# full_schema.net
KiCad netlist of a schematic drawn in EAGLE
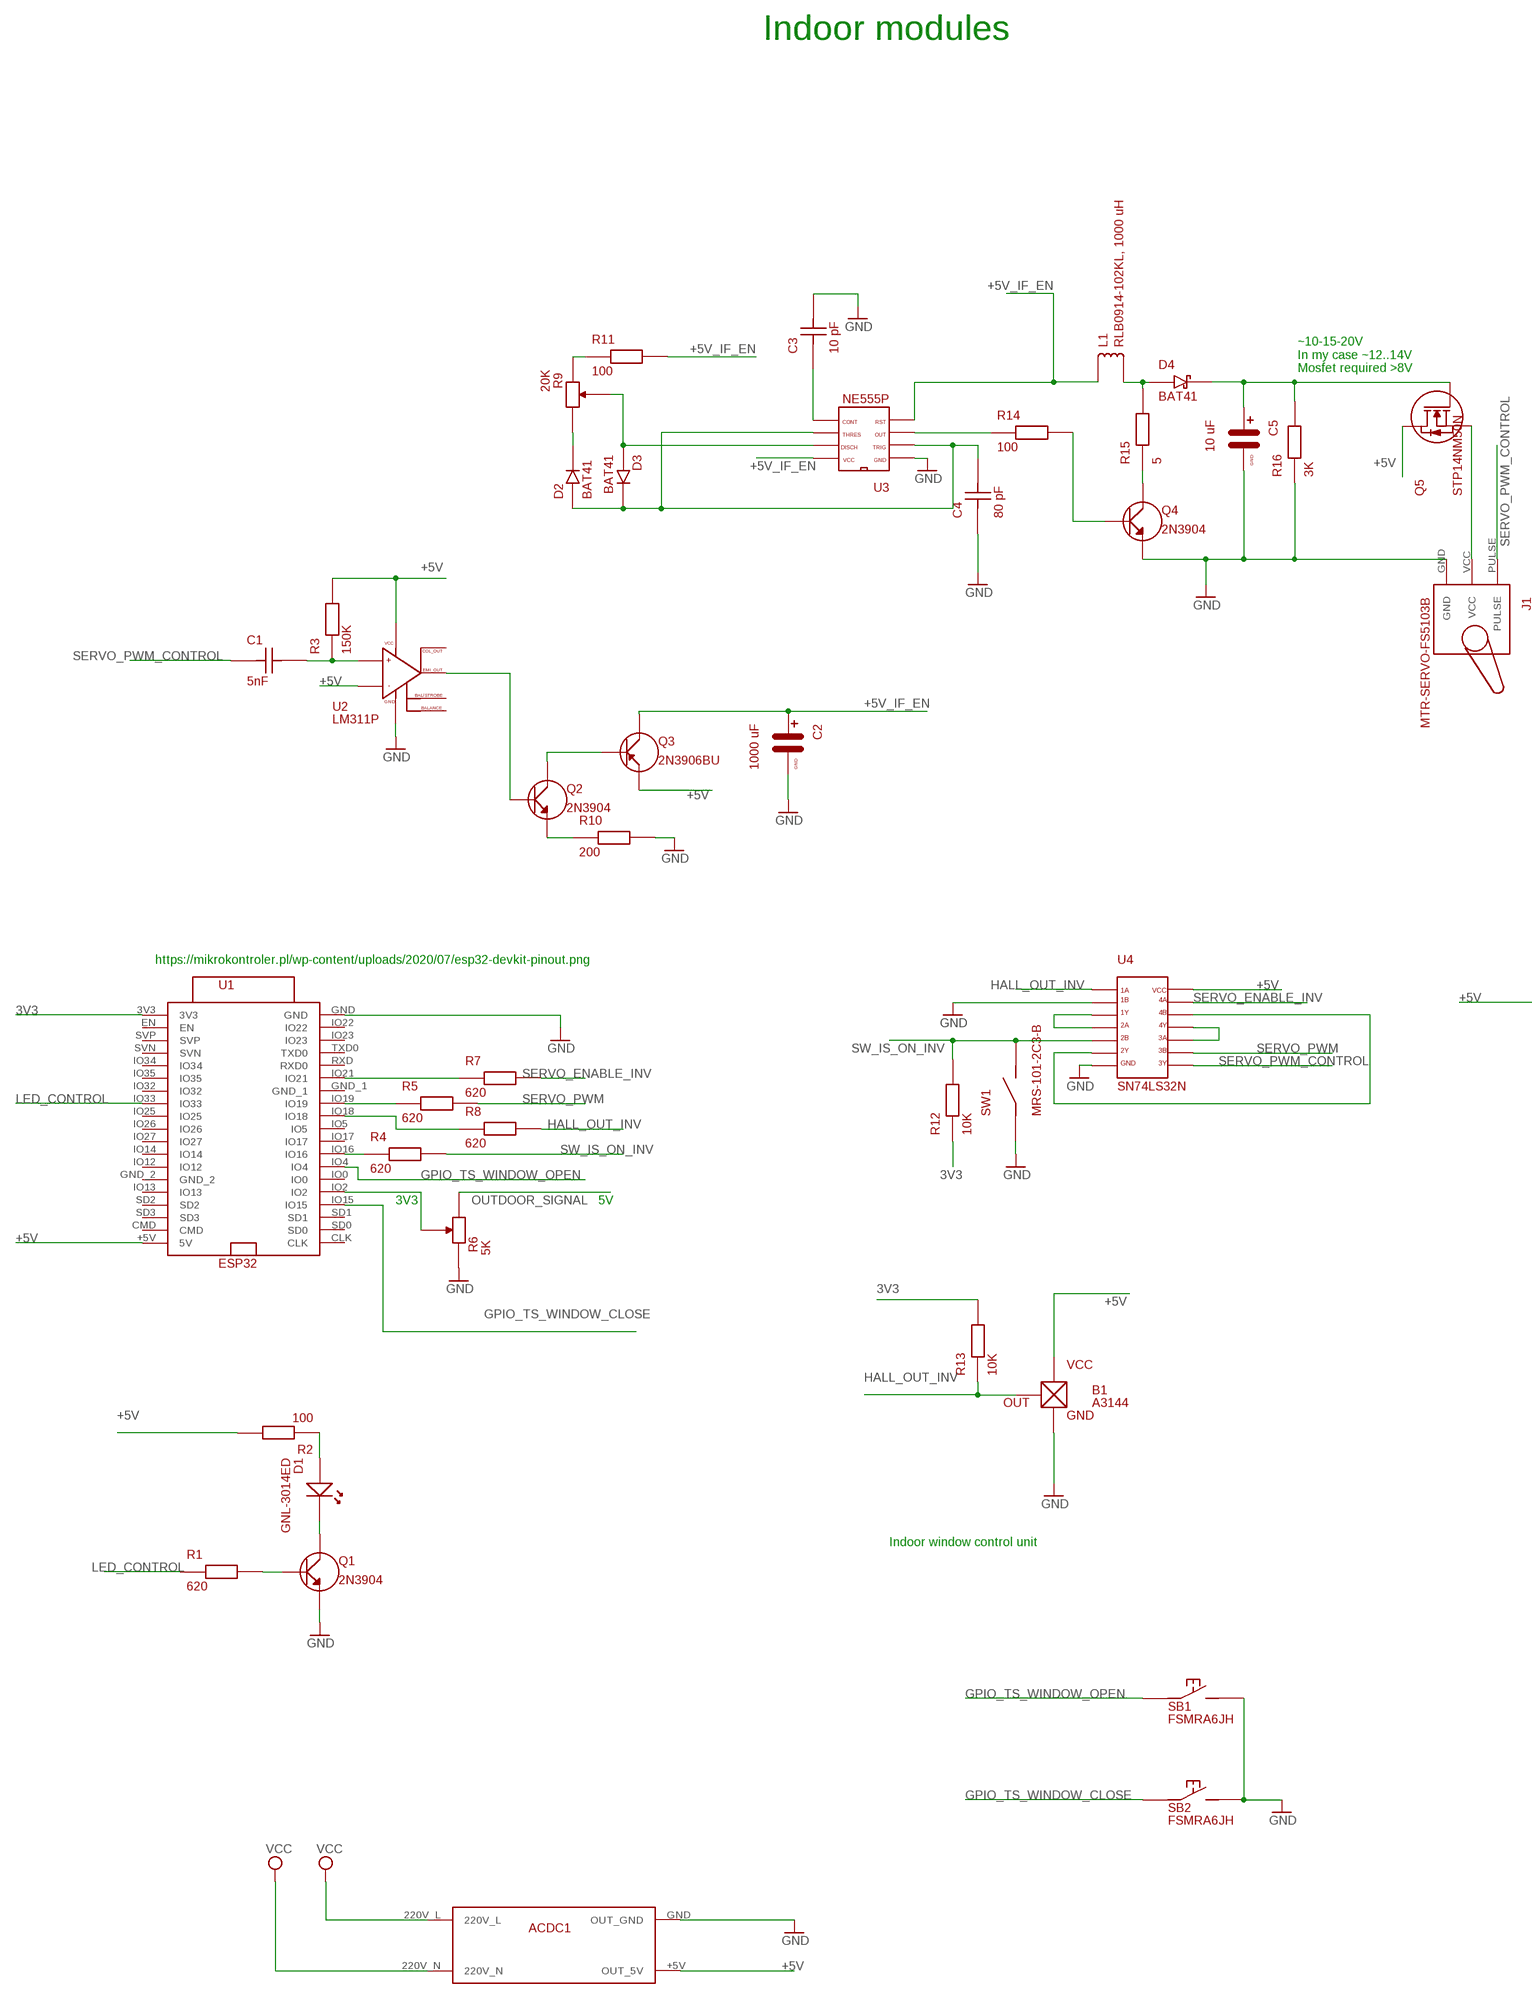
[diagram p0: schematic, sheet 1, part 1 of 2]
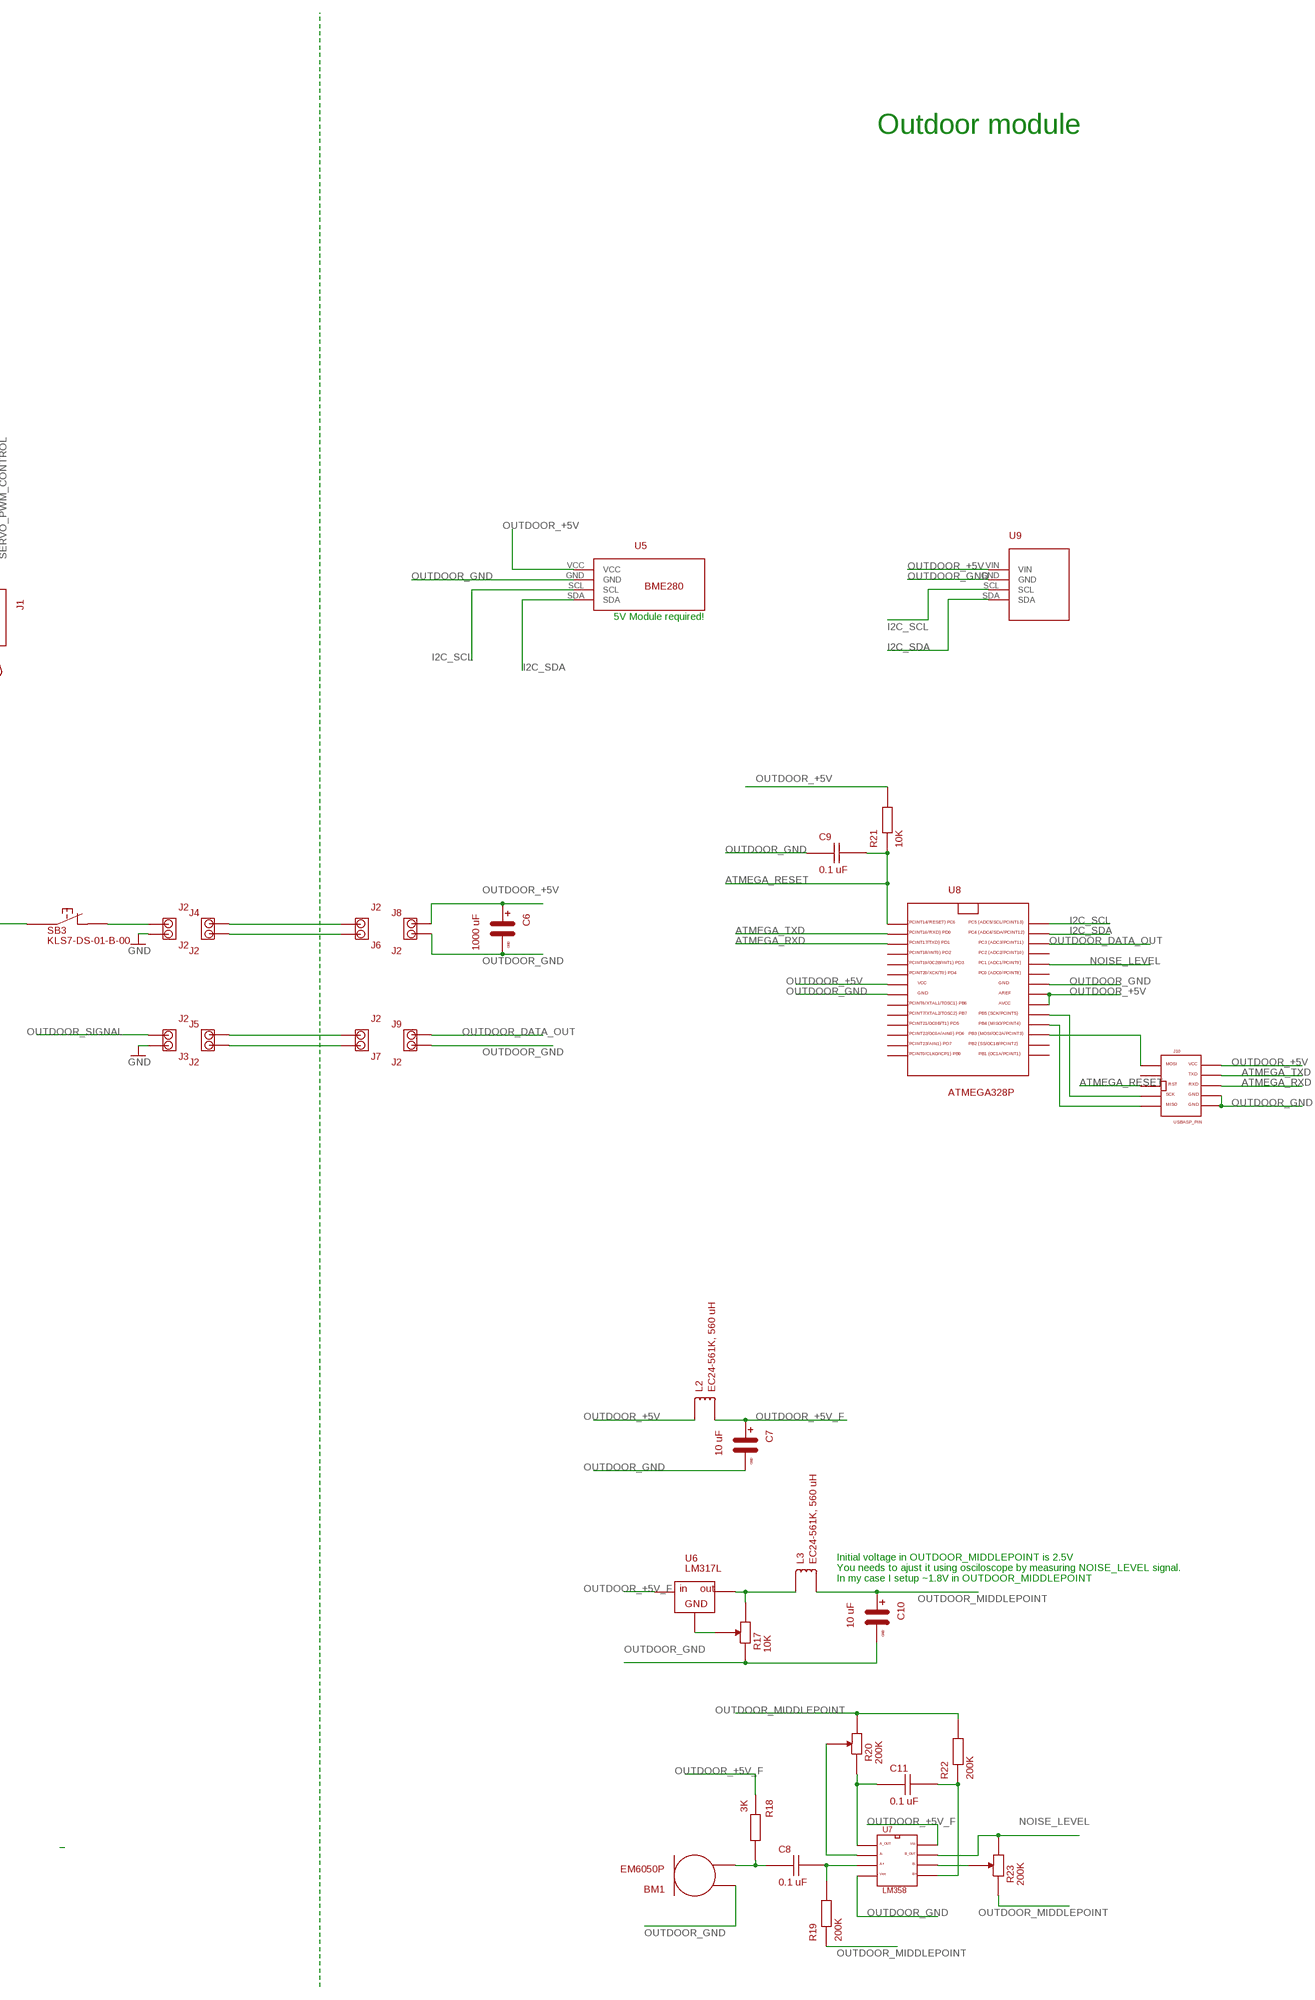
[diagram p1: schematic, sheet 1, part 2 of 2]

(export (version "E")
  (design (tool "Eeschema 10.0.6"))
  (components
    (comp (ref "ACDC1")
      (value "ACDC")
      (footprint "eagle-import:ACDC")
      (libsource (lib "eagle-import") (part "ACDC"))
    )
    (comp (ref "B1")
      (value "A3144")
      (footprint "eagle-import:HALL_SENSOR")
      (libsource (lib "eagle-import") (part "HALL_SENSOR"))
    )
    (comp (ref "BM1")
      (value "EM6050P")
      (footprint "eagle-import:MICROPHONE")
      (libsource (lib "eagle-import") (part "MICROPHONE"))
    )
    (comp (ref "C1")
      (value "5nF")
      (footprint "eagle-import:C-1")
      (libsource (lib "eagle-import") (part "C-1"))
    )
    (comp (ref "C2")
      (value "1000 uF")
      (footprint "eagle-import:C")
      (libsource (lib "eagle-import") (part "C"))
    )
    (comp (ref "C3")
      (value "10 pF")
      (footprint "eagle-import:C-1")
      (libsource (lib "eagle-import") (part "C-1"))
    )
    (comp (ref "C4")
      (value "80 pF")
      (footprint "eagle-import:C-1")
      (libsource (lib "eagle-import") (part "C-1"))
    )
    (comp (ref "C5") (value "10 uF") (footprint "eagle-import:C") (libsource (lib "eagle-import") (part "C")))
    (comp (ref "C6")
      (value "1000 uF")
      (footprint "eagle-import:C")
      (libsource (lib "eagle-import") (part "C"))
    )
    (comp (ref "C7") (value "10 uF") (footprint "eagle-import:C") (libsource (lib "eagle-import") (part "C")))
    (comp (ref "C8")
      (value "0.1 uF")
      (footprint "eagle-import:C-1")
      (libsource (lib "eagle-import") (part "C-1"))
    )
    (comp (ref "C9")
      (value "0.1 uF")
      (footprint "eagle-import:C-1")
      (libsource (lib "eagle-import") (part "C-1"))
    )
    (comp (ref "C10")
      (value "10 uF")
      (footprint "eagle-import:C")
      (libsource (lib "eagle-import") (part "C"))
    )
    (comp (ref "C11")
      (value "0.1 uF")
      (footprint "eagle-import:C-1")
      (libsource (lib "eagle-import") (part "C-1"))
    )
    (comp (ref "D1")
      (value "GNL-3014ED")
      (footprint "eagle-import:LD")
      (libsource (lib "eagle-import") (part "LD"))
    )
    (comp (ref "D2") (value "BAT41") (footprint "eagle-import:D") (libsource (lib "eagle-import") (part "D")))
    (comp (ref "D3") (value "BAT41") (footprint "eagle-import:D") (libsource (lib "eagle-import") (part "D")))
    (comp (ref "D4")
      (value "BAT41")
      (footprint "eagle-import:D_SCHOTTKY")
      (libsource (lib "eagle-import") (part "D_SCHOTTKY"))
    )
    (comp (ref "J1")
      (value "MTR-SERVO-FS5103B")
      (footprint "eagle-import:SERVO")
      (libsource (lib "eagle-import") (part "SERVO"))
    )
    (comp (ref "J2") (value "J2") (footprint "eagle-import:J2") (libsource (lib "eagle-import") (part "J2")))
    (comp (ref "J3") (value "J2") (footprint "eagle-import:J2") (libsource (lib "eagle-import") (part "J2")))
    (comp (ref "J4") (value "J2") (footprint "eagle-import:J2") (libsource (lib "eagle-import") (part "J2")))
    (comp (ref "J5") (value "J2") (footprint "eagle-import:J2") (libsource (lib "eagle-import") (part "J2")))
    (comp (ref "J6") (value "J2") (footprint "eagle-import:J2") (libsource (lib "eagle-import") (part "J2")))
    (comp (ref "J7") (value "J2") (footprint "eagle-import:J2") (libsource (lib "eagle-import") (part "J2")))
    (comp (ref "J8") (value "J2") (footprint "eagle-import:J2") (libsource (lib "eagle-import") (part "J2")))
    (comp (ref "J9") (value "J2") (footprint "eagle-import:J2") (libsource (lib "eagle-import") (part "J2")))
    (comp (ref "J10")
      (value "USBASP_PIN")
      (footprint "eagle-import:USBASP_PIN")
      (libsource (lib "eagle-import") (part "USBASP_PIN"))
    )
    (comp (ref "L1")
      (value "RLB0914-102KL, 1000 uH")
      (footprint "eagle-import:L-RLB0914")
      (libsource (lib "eagle-import") (part "L"))
    )
    (comp (ref "L2")
      (value "EC24-561K, 560 uH")
      (footprint "eagle-import:L-EC24")
      (libsource (lib "eagle-import") (part "LL-EC24"))
    )
    (comp (ref "L3")
      (value "EC24-561K, 560 uH")
      (footprint "eagle-import:L-EC24")
      (libsource (lib "eagle-import") (part "LL-EC24"))
    )
    (comp (ref "Q1")
      (value "2N3904")
      (footprint "eagle-import:TRANSISTOR")
      (libsource (lib "eagle-import") (part "TRANSISTOR_NPN"))
    )
    (comp (ref "Q2")
      (value "2N3904")
      (footprint "eagle-import:TRANSISTOR")
      (libsource (lib "eagle-import") (part "TRANSISTOR_NPN"))
    )
    (comp (ref "Q3")
      (value "2N3906BU")
      (footprint "eagle-import:TRANSISTOR")
      (libsource (lib "eagle-import") (part "TRANSISTOR_PNP"))
    )
    (comp (ref "Q4")
      (value "2N3904")
      (footprint "eagle-import:TRANSISTOR")
      (libsource (lib "eagle-import") (part "TRANSISTOR_NPN"))
    )
    (comp (ref "Q5")
      (value "STP14NM50N")
      (footprint "eagle-import:MOSFET_N")
      (libsource (lib "eagle-import") (part "MOSFET_N"))
    )
    (comp (ref "R1") (value "620") (footprint "eagle-import:R") (libsource (lib "eagle-import") (part "R")))
    (comp (ref "R2") (value "100") (footprint "eagle-import:R") (libsource (lib "eagle-import") (part "R")))
    (comp (ref "R3") (value "150K") (footprint "eagle-import:R") (libsource (lib "eagle-import") (part "R")))
    (comp (ref "R4") (value "620") (footprint "eagle-import:R") (libsource (lib "eagle-import") (part "R")))
    (comp (ref "R5") (value "620") (footprint "eagle-import:R") (libsource (lib "eagle-import") (part "R")))
    (comp (ref "R6")
      (value "5K")
      (footprint "eagle-import:RD-3362H")
      (libsource (lib "eagle-import") (part "RD"))
    )
    (comp (ref "R7") (value "620") (footprint "eagle-import:R") (libsource (lib "eagle-import") (part "R")))
    (comp (ref "R8") (value "620") (footprint "eagle-import:R") (libsource (lib "eagle-import") (part "R")))
    (comp (ref "R9")
      (value "20K")
      (footprint "eagle-import:RD-3362H")
      (libsource (lib "eagle-import") (part "RD"))
    )
    (comp (ref "R10") (value "200") (footprint "eagle-import:R") (libsource (lib "eagle-import") (part "R")))
    (comp (ref "R11") (value "100") (footprint "eagle-import:R") (libsource (lib "eagle-import") (part "R")))
    (comp (ref "R12") (value "10K") (footprint "eagle-import:R") (libsource (lib "eagle-import") (part "R")))
    (comp (ref "R13") (value "10K") (footprint "eagle-import:R") (libsource (lib "eagle-import") (part "R")))
    (comp (ref "R14") (value "100") (footprint "eagle-import:R") (libsource (lib "eagle-import") (part "R")))
    (comp (ref "R15") (value "5") (footprint "eagle-import:R") (libsource (lib "eagle-import") (part "R")))
    (comp (ref "R16") (value "3K") (footprint "eagle-import:R") (libsource (lib "eagle-import") (part "R")))
    (comp (ref "R17")
      (value "10K")
      (footprint "eagle-import:RD-3362H")
      (libsource (lib "eagle-import") (part "RD"))
    )
    (comp (ref "R18") (value "3K") (footprint "eagle-import:R") (libsource (lib "eagle-import") (part "R")))
    (comp (ref "R19") (value "200K") (footprint "eagle-import:R") (libsource (lib "eagle-import") (part "R")))
    (comp (ref "R20")
      (value "200K")
      (footprint "eagle-import:RD-3296Z")
      (libsource (lib "eagle-import") (part "RD3296-Z"))
    )
    (comp (ref "R21") (value "10K") (footprint "eagle-import:R") (libsource (lib "eagle-import") (part "R")))
    (comp (ref "R22") (value "200K") (footprint "eagle-import:R") (libsource (lib "eagle-import") (part "R")))
    (comp (ref "R23")
      (value "200K")
      (footprint "eagle-import:RD-3296Z")
      (libsource (lib "eagle-import") (part "RD3296-Z"))
    )
    (comp (ref "SB1")
      (value "FSMRA6JH")
      (footprint "eagle-import:SB-NO-SPST-ANGLE")
      (libsource (lib "eagle-import") (part "SB-NO"))
    )
    (comp (ref "SB2")
      (value "FSMRA6JH")
      (footprint "eagle-import:SB-NO-SPST-ANGLE")
      (libsource (lib "eagle-import") (part "SB-NO"))
    )
    (comp (ref "SB3")
      (value "KLS7-DS-01-B-00")
      (footprint "eagle-import:SB-NC")
      (libsource (lib "eagle-import") (part "SB-NC"))
    )
    (comp (ref "SW1")
      (value "MRS-101-2C3-B")
      (footprint "eagle-import:SWITCH")
      (libsource (lib "eagle-import") (part "SWITCH"))
    )
    (comp (ref "U1")
      (value "ESP32")
      (footprint "eagle-import:ESP32")
      (libsource (lib "eagle-import") (part "ESP32"))
    )
    (comp (ref "U2")
      (value "LM311P")
      (footprint "eagle-import:DIP8")
      (libsource (lib "eagle-import") (part "LM311P"))
    )
    (comp (ref "U3")
      (value "NE555P")
      (footprint "eagle-import:DIP8")
      (libsource (lib "eagle-import") (part "NE555P"))
    )
    (comp (ref "U4")
      (value "SN74LS32N")
      (footprint "eagle-import:DIP14")
      (libsource (lib "eagle-import") (part "SN74LS32N"))
    )
    (comp (ref "U5")
      (value "BMP280 5V module")
      (footprint "eagle-import:BME280")
      (libsource (lib "eagle-import") (part "BME280"))
    )
    (comp (ref "U6")
      (value "LM317L")
      (footprint "eagle-import:VOLTAGE_REGULATOR")
      (libsource (lib "eagle-import") (part "VOLTAGE_REGULATOR"))
    )
    (comp (ref "U7")
      (value "LM358")
      (footprint "eagle-import:DIP8")
      (libsource (lib "eagle-import") (part "LM358"))
    )
    (comp (ref "U8")
      (value "ATMEGA328P")
      (footprint "eagle-import:ATMEGA328P")
      (libsource (lib "eagle-import") (part "ATMEGA328P"))
    )
    (comp (ref "U9")
      (value "GY-SGP30")
      (footprint "eagle-import:GY-SGP30")
      (libsource (lib "eagle-import") (part "GY-SGP30"))
    )
  )
  (nets
    (net (code "1") (name "/+5V") (class "Default")
      (node (ref "ACDC1") (pin "+5V") (pinfunction "OUT_5V_+5V") (pintype "power_in"))
      (node (ref "B1") (pin "VCC") (pinfunction "VCC_VCC") (pintype "power_in"))
      (node (ref "Q3") (pin "E") (pinfunction "E_E") (pintype "bidirectional"))
      (node (ref "Q5") (pin "D") (pinfunction "D_D") (pintype "bidirectional"))
      (node (ref "R2") (pin "P$2") (pinfunction "P$2_P$2") (pintype "bidirectional"))
      (node (ref "R3") (pin "P$2") (pinfunction "P$2_P$2") (pintype "bidirectional"))
      (node (ref "SB3") (pin "P$1") (pinfunction "P$1_P$1") (pintype "bidirectional"))
      (node (ref "U1") (pin "+5V") (pinfunction "5V_+5V") (pintype "power_in"))
      (node (ref "U2") (pin "PIN_3") (pinfunction "IN-_PIN_3") (pintype "input"))
      (node (ref "U2") (pin "PIN_8") (pinfunction "VCC_PIN_8") (pintype "power_in"))
      (node (ref "U4") (pin "PIN_14") (pinfunction "VCC_PIN_14") (pintype "power_in"))
    )
    (net (code "2") (name "/+5V_IF_EN") (class "Default")
      (node (ref "C2") (pin "PIN_PLUS") (pinfunction "PIN_PLUS_PIN_PLUS") (pintype "bidirectional"))
      (node (ref "L1") (pin "P$1") (pinfunction "P$1_P$1") (pintype "bidirectional"))
      (node (ref "Q3") (pin "C") (pinfunction "C_C") (pintype "bidirectional"))
      (node (ref "R11") (pin "P$2") (pinfunction "P$2_P$2") (pintype "bidirectional"))
      (node (ref "U3") (pin "PIN_4") (pinfunction "RESET_PIN_4") (pintype "bidirectional"))
      (node (ref "U3") (pin "PIN_8") (pinfunction "VCC_PIN_8") (pintype "power_in"))
    )
    (net (code "3") (name "/3V3") (class "Default")
      (node (ref "R12") (pin "P$1") (pinfunction "P$1_P$1") (pintype "bidirectional"))
      (node (ref "R13") (pin "P$2") (pinfunction "P$2_P$2") (pintype "bidirectional"))
      (node (ref "U1") (pin "3V3") (pinfunction "3V3_3V3") (pintype "power_in"))
    )
    (net (code "4") (name "/ATMEGA_RESET") (class "Default")
      (node (ref "C9") (pin "P$2") (pinfunction "P$2_P$2") (pintype "bidirectional"))
      (node (ref "J10") (pin "RST") (pinfunction "RESET_RST") (pintype "bidirectional"))
      (node (ref "R21") (pin "P$1") (pinfunction "P$1_P$1") (pintype "bidirectional"))
      (node (ref "U8") (pin "PC6") (pinfunction "PC6_PC6") (pintype "bidirectional"))
    )
    (net (code "5") (name "/ATMEGA_RXD") (class "Default")
      (node (ref "J10") (pin "RXD") (pinfunction "RXD_RXD") (pintype "bidirectional"))
      (node (ref "U8") (pin "PD1") (pinfunction "PD1_PD1") (pintype "bidirectional"))
    )
    (net (code "6") (name "/ATMEGA_TXD") (class "Default")
      (node (ref "J10") (pin "TXD") (pinfunction "TXD_TXD") (pintype "bidirectional"))
      (node (ref "U8") (pin "PD0") (pinfunction "PD0_PD0") (pintype "bidirectional"))
    )
    (net (code "7") (name "/GPIO_TS_WINDOW_CLOSE") (class "Default")
      (node (ref "SB2") (pin "A") (pinfunction "P$1_A") (pintype "bidirectional"))
      (node (ref "U1") (pin "IO15") (pinfunction "IO15_IO15") (pintype "bidirectional"))
    )
    (net (code "8") (name "/GPIO_TS_WINDOW_OPEN") (class "Default")
      (node (ref "SB1") (pin "A") (pinfunction "P$1_A") (pintype "bidirectional"))
      (node (ref "U1") (pin "IO4") (pinfunction "IO4_IO4") (pintype "bidirectional"))
    )
    (net (code "9") (name "/HALL_OUT_INV") (class "Default")
      (node (ref "B1") (pin "OUT") (pinfunction "OUT_OUT") (pintype "bidirectional"))
      (node (ref "R13") (pin "P$1") (pinfunction "P$1_P$1") (pintype "bidirectional"))
      (node (ref "R8") (pin "P$2") (pinfunction "P$2_P$2") (pintype "bidirectional"))
      (node (ref "U4") (pin "PIN_1") (pinfunction "1A_PIN_1") (pintype "input"))
    )
    (net (code "10") (name "/I2C_SCL") (class "Default")
      (node (ref "U5") (pin "SCL") (pinfunction "SCL_SCL") (pintype "bidirectional"))
      (node (ref "U8") (pin "PC5") (pinfunction "PC5_PC5") (pintype "bidirectional"))
      (node (ref "U9") (pin "SCL") (pinfunction "SCL_SCL") (pintype "bidirectional"))
    )
    (net (code "11") (name "/I2C_SDA") (class "Default")
      (node (ref "U5") (pin "SDA") (pinfunction "SDA_SDA") (pintype "bidirectional"))
      (node (ref "U8") (pin "PC4") (pinfunction "PC4_PC4") (pintype "bidirectional"))
      (node (ref "U9") (pin "SDA") (pinfunction "SDA_SDA") (pintype "bidirectional"))
    )
    (net (code "12") (name "/LED_CONTROL") (class "Default")
      (node (ref "R1") (pin "P$1") (pinfunction "P$1_P$1") (pintype "bidirectional"))
      (node (ref "U1") (pin "IO33") (pinfunction "IO33_IO33") (pintype "bidirectional"))
    )
    (net (code "13") (name "/NOISE_LEVEL") (class "Default")
      (node (ref "R23") (pin "P2") (pinfunction "P2_P2") (pintype "bidirectional"))
      (node (ref "U7") (pin "PIN_7") (pinfunction "B_OUT_PIN_7") (pintype "output"))
      (node (ref "U8") (pin "PC1") (pinfunction "PC1_PC1") (pintype "bidirectional"))
    )
    (net (code "14") (name "/OUTDOOR_+5V") (class "Default")
      (node (ref "C6") (pin "PIN_PLUS") (pinfunction "PIN_PLUS_PIN_PLUS") (pintype "bidirectional"))
      (node (ref "J10") (pin "VCC") (pinfunction "VCC_VCC") (pintype "power_in"))
      (node (ref "J8") (pin "PIN_1") (pinfunction "PIN_1_PIN_1") (pintype "bidirectional"))
      (node (ref "L2") (pin "P$1") (pinfunction "P$1_P$1") (pintype "bidirectional"))
      (node (ref "R21") (pin "P$2") (pinfunction "P$2_P$2") (pintype "bidirectional"))
      (node (ref "U5") (pin "VCC") (pinfunction "VCC_VCC") (pintype "power_in"))
      (node (ref "U8") (pin "AREF") (pinfunction "AREF_AREF") (pintype "bidirectional"))
      (node (ref "U8") (pin "AVCC") (pinfunction "AVCC_AVCC") (pintype "power_in"))
      (node (ref "U8") (pin "VCC") (pinfunction "VCC_VCC") (pintype "power_in"))
      (node (ref "U9") (pin "VIN") (pinfunction "VIN_VIN") (pintype "power_in"))
    )
    (net (code "15") (name "/OUTDOOR_+5V_F") (class "Default")
      (node (ref "C7") (pin "PIN_PLUS") (pinfunction "PIN_PLUS_PIN_PLUS") (pintype "bidirectional"))
      (node (ref "L2") (pin "P$2") (pinfunction "P$2_P$2") (pintype "bidirectional"))
      (node (ref "R18") (pin "P$1") (pinfunction "P$1_P$1") (pintype "bidirectional"))
      (node (ref "U6") (pin "IN") (pinfunction "IN_IN") (pintype "power_in"))
      (node (ref "U7") (pin "PIN_8") (pinfunction "VCC_PIN_8") (pintype "power_in"))
    )
    (net (code "16") (name "/OUTDOOR_DATA_OUT") (class "Default")
      (node (ref "J9") (pin "PIN_1") (pinfunction "PIN_1_PIN_1") (pintype "bidirectional"))
      (node (ref "U8") (pin "PC3") (pinfunction "PC3_PC3") (pintype "bidirectional"))
    )
    (net (code "17") (name "/OUTDOOR_GND") (class "Default")
      (node (ref "BM1") (pin "P$1") (pinfunction "P$1_P$1") (pintype "bidirectional"))
      (node (ref "C10") (pin "PIN_GND") (pinfunction "PIN_GND_PIN_GND") (pintype "bidirectional"))
      (node (ref "C6") (pin "PIN_GND") (pinfunction "PIN_GND_PIN_GND") (pintype "bidirectional"))
      (node (ref "C7") (pin "PIN_GND") (pinfunction "PIN_GND_PIN_GND") (pintype "bidirectional"))
      (node (ref "C9") (pin "P$1") (pinfunction "P$1_P$1") (pintype "bidirectional"))
      (node (ref "J10") (pin "GND") (pinfunction "GND_GND") (pintype "power_in"))
      (node (ref "J10") (pin "GND1") (pinfunction "GND1_GND1") (pintype "power_in"))
      (node (ref "J8") (pin "PIN_2") (pinfunction "PIN_2_PIN_2") (pintype "bidirectional"))
      (node (ref "J9") (pin "PIN_2") (pinfunction "PIN_2_PIN_2") (pintype "bidirectional"))
      (node (ref "R17") (pin "P1") (pinfunction "P1_P1") (pintype "bidirectional"))
      (node (ref "U5") (pin "GND") (pinfunction "GND_GND") (pintype "power_in"))
      (node (ref "U7") (pin "PIN_4") (pinfunction "VEE_PIN_4") (pintype "power_in"))
      (node (ref "U8") (pin "GND") (pinfunction "GND_GND") (pintype "power_in"))
      (node (ref "U8") (pin "GND1") (pinfunction "GND1_GND1") (pintype "power_in"))
      (node (ref "U9") (pin "GND") (pinfunction "GND_GND") (pintype "power_in"))
    )
    (net (code "18") (name "/OUTDOOR_MIDDLEPOINT") (class "Default")
      (node (ref "C10") (pin "PIN_PLUS") (pinfunction "PIN_PLUS_PIN_PLUS") (pintype "bidirectional"))
      (node (ref "L3") (pin "P$2") (pinfunction "P$2_P$2") (pintype "bidirectional"))
      (node (ref "R19") (pin "P$1") (pinfunction "P$1_P$1") (pintype "bidirectional"))
      (node (ref "R20") (pin "P2") (pinfunction "P2_P2") (pintype "bidirectional"))
      (node (ref "R22") (pin "P$2") (pinfunction "P$2_P$2") (pintype "bidirectional"))
      (node (ref "R23") (pin "P1") (pinfunction "P1_P1") (pintype "bidirectional"))
    )
    (net (code "19") (name "/OUTDOOR_SIGNAL") (class "Default")
      (node (ref "J3") (pin "PIN_2") (pinfunction "PIN_2_PIN_2") (pintype "bidirectional"))
      (node (ref "R6") (pin "P2") (pinfunction "P2_P2") (pintype "bidirectional"))
    )
    (net (code "20") (name "/SERVO_ENABLE_INV") (class "Default")
      (node (ref "R7") (pin "P$2") (pinfunction "P$2_P$2") (pintype "bidirectional"))
      (node (ref "U4") (pin "PIN_13") (pinfunction "4A_PIN_13") (pintype "input"))
    )
    (net (code "21") (name "/SERVO_PWM") (class "Default")
      (node (ref "R5") (pin "P$2") (pinfunction "P$2_P$2") (pintype "bidirectional"))
      (node (ref "U4") (pin "PIN_9") (pinfunction "3B_PIN_9") (pintype "input"))
    )
    (net (code "22") (name "/SERVO_PWM_CONTROL") (class "Default")
      (node (ref "C1") (pin "P$1") (pinfunction "P$1_P$1") (pintype "bidirectional"))
      (node (ref "J1") (pin "PULSE") (pinfunction "PULSE_PULSE") (pintype "input"))
      (node (ref "U4") (pin "PIN_8") (pinfunction "3Y_PIN_8") (pintype "output"))
    )
    (net (code "23") (name "/SW_IS_ON_INV") (class "Default")
      (node (ref "R12") (pin "P$2") (pinfunction "P$2_P$2") (pintype "bidirectional"))
      (node (ref "R4") (pin "P$2") (pinfunction "P$2_P$2") (pintype "bidirectional"))
      (node (ref "SW1") (pin "P$2") (pinfunction "P$2_P$2") (pintype "bidirectional"))
      (node (ref "U4") (pin "PIN_5") (pinfunction "2B_PIN_5") (pintype "input"))
    )
    (net (code "24") (name "GND") (class "Default")
      (node (ref "ACDC1") (pin "GND") (pinfunction "OUT_GND_GND") (pintype "power_in"))
      (node (ref "B1") (pin "GND") (pinfunction "GND_GND") (pintype "power_in"))
      (node (ref "C2") (pin "PIN_GND") (pinfunction "PIN_GND_PIN_GND") (pintype "bidirectional"))
      (node (ref "C3") (pin "P$2") (pinfunction "P$2_P$2") (pintype "bidirectional"))
      (node (ref "C4") (pin "P$1") (pinfunction "P$1_P$1") (pintype "bidirectional"))
      (node (ref "C5") (pin "PIN_GND") (pinfunction "PIN_GND_PIN_GND") (pintype "bidirectional"))
      (node (ref "J1") (pin "GND") (pinfunction "GND_GND") (pintype "power_in"))
      (node (ref "J2") (pin "PIN_1") (pinfunction "PIN_1_PIN_1") (pintype "bidirectional"))
      (node (ref "J3") (pin "PIN_1") (pinfunction "PIN_1_PIN_1") (pintype "bidirectional"))
      (node (ref "Q1") (pin "E") (pinfunction "E_E") (pintype "bidirectional"))
      (node (ref "Q4") (pin "E") (pinfunction "E_E") (pintype "bidirectional"))
      (node (ref "R10") (pin "P$2") (pinfunction "P$2_P$2") (pintype "bidirectional"))
      (node (ref "R16") (pin "P$1") (pinfunction "P$1_P$1") (pintype "bidirectional"))
      (node (ref "R6") (pin "P1") (pinfunction "P1_P1") (pintype "bidirectional"))
      (node (ref "SB1") (pin "B") (pinfunction "P$2_B") (pintype "bidirectional"))
      (node (ref "SB2") (pin "B") (pinfunction "P$2_B") (pintype "bidirectional"))
      (node (ref "SW1") (pin "P$1") (pinfunction "P$1_P$1") (pintype "bidirectional"))
      (node (ref "U1") (pin "GND") (pinfunction "GND_GND") (pintype "power_in"))
      (node (ref "U2") (pin "PIN_4") (pinfunction "GND_PIN_4") (pintype "power_in"))
      (node (ref "U3") (pin "PIN_1") (pinfunction "GND_PIN_1") (pintype "power_in"))
      (node (ref "U4") (pin "PIN_2") (pinfunction "1B_PIN_2") (pintype "input"))
      (node (ref "U4") (pin "PIN_7") (pinfunction "GND_PIN_7") (pintype "power_in"))
    )
    (net (code "25") (name "Net-(BM1-PadP$2)") (class "Default")
      (node (ref "BM1") (pin "P$2") (pinfunction "P$2_P$2") (pintype "bidirectional"))
      (node (ref "C8") (pin "P$1") (pinfunction "P$1_P$1") (pintype "bidirectional"))
      (node (ref "R18") (pin "P$2") (pinfunction "P$2_P$2") (pintype "bidirectional"))
    )
    (net (code "26") (name "Net-(C5-PadPIN_PLUS)") (class "Default")
      (node (ref "C5") (pin "PIN_PLUS") (pinfunction "PIN_PLUS_PIN_PLUS") (pintype "bidirectional"))
      (node (ref "D4") (pin "CATHODE") (pinfunction "CATHODE_CATHODE") (pintype "bidirectional"))
      (node (ref "Q5") (pin "G") (pinfunction "G_G") (pintype "bidirectional"))
      (node (ref "R16") (pin "P$2") (pinfunction "P$2_P$2") (pintype "bidirectional"))
    )
    (net (code "27") (name "Net-(D1-PadPIN_ANODE)") (class "Default")
      (node (ref "D1") (pin "PIN_ANODE") (pinfunction "PIN_ANODE_PIN_ANODE") (pintype "bidirectional"))
      (node (ref "Q1") (pin "C") (pinfunction "C_C") (pintype "bidirectional"))
    )
    (net (code "28") (name "Net-(D1-PadPIN_CATHODE)") (class "Default")
      (node (ref "D1") (pin "PIN_CATHODE") (pinfunction "PIN_CATHODE_PIN_CATHODE") (pintype "bidirectional"))
      (node (ref "R2") (pin "P$1") (pinfunction "P$1_P$1") (pintype "bidirectional"))
    )
    (net (code "29") (name "Net-(D2-PadP$2)") (class "Default")
      (node (ref "D2") (pin "P$2") (pinfunction "P$2_P$2") (pintype "bidirectional"))
      (node (ref "R9") (pin "P2") (pinfunction "P2_P2") (pintype "bidirectional"))
    )
    (net (code "30") (name "Net-(D4-PadANODE)") (class "Default")
      (node (ref "D4") (pin "ANODE") (pinfunction "ANODE_ANODE") (pintype "bidirectional"))
      (node (ref "L1") (pin "P$2") (pinfunction "P$2_P$2") (pintype "bidirectional"))
      (node (ref "R15") (pin "P$2") (pinfunction "P$2_P$2") (pintype "bidirectional"))
    )
    (net (code "31") (name "Net-(J1-PadVCC)") (class "Default")
      (node (ref "J1") (pin "VCC") (pinfunction "VCC_VCC") (pintype "power_in"))
      (node (ref "Q5") (pin "S") (pinfunction "S_S") (pintype "bidirectional"))
    )
    (net (code "32") (name "Net-(J2-PadPIN_2)") (class "Default")
      (node (ref "J2") (pin "PIN_2") (pinfunction "PIN_2_PIN_2") (pintype "bidirectional"))
      (node (ref "SB3") (pin "P$2") (pinfunction "P$2_P$2") (pintype "bidirectional"))
    )
    (net (code "33") (name "Net-(J4-PadPIN_1)") (class "Default")
      (node (ref "J4") (pin "PIN_1") (pinfunction "PIN_1_PIN_1") (pintype "bidirectional"))
      (node (ref "J6") (pin "PIN_2") (pinfunction "PIN_2_PIN_2") (pintype "bidirectional"))
    )
    (net (code "34") (name "Net-(J4-PadPIN_2)") (class "Default")
      (node (ref "J4") (pin "PIN_2") (pinfunction "PIN_2_PIN_2") (pintype "bidirectional"))
      (node (ref "J6") (pin "PIN_1") (pinfunction "PIN_1_PIN_1") (pintype "bidirectional"))
    )
    (net (code "35") (name "Net-(J5-PadPIN_1)") (class "Default")
      (node (ref "J5") (pin "PIN_1") (pinfunction "PIN_1_PIN_1") (pintype "bidirectional"))
      (node (ref "J7") (pin "PIN_2") (pinfunction "PIN_2_PIN_2") (pintype "bidirectional"))
    )
    (net (code "36") (name "Net-(J5-PadPIN_2)") (class "Default")
      (node (ref "J5") (pin "PIN_2") (pinfunction "PIN_2_PIN_2") (pintype "bidirectional"))
      (node (ref "J7") (pin "PIN_1") (pinfunction "PIN_1_PIN_1") (pintype "bidirectional"))
    )
    (net (code "37") (name "Net-(J10-PadMISO)") (class "Default")
      (node (ref "J10") (pin "MISO") (pinfunction "MISO_MISO") (pintype "bidirectional"))
      (node (ref "U8") (pin "PB4") (pinfunction "PB4_PB4") (pintype "bidirectional"))
    )
    (net (code "38") (name "Net-(J10-PadMOSI)") (class "Default")
      (node (ref "J10") (pin "MOSI") (pinfunction "MOSI_MOSI") (pintype "bidirectional"))
      (node (ref "U8") (pin "PB3") (pinfunction "PB3_PB3") (pintype "bidirectional"))
    )
    (net (code "39") (name "Net-(J10-PadSCK)") (class "Default")
      (node (ref "J10") (pin "SCK") (pinfunction "SCK_SCK") (pintype "bidirectional"))
      (node (ref "U8") (pin "PB5") (pinfunction "PB5_PB5") (pintype "bidirectional"))
    )
    (net (code "40") (name "Net-(L3-PadP$1)") (class "Default")
      (node (ref "L3") (pin "P$1") (pinfunction "P$1_P$1") (pintype "bidirectional"))
      (node (ref "R17") (pin "P2") (pinfunction "P2_P2") (pintype "bidirectional"))
      (node (ref "U6") (pin "OUT") (pinfunction "OUT_OUT") (pintype "power_in"))
    )
    (net (code "41") (name "Net-(Q1-PadB)") (class "Default")
      (node (ref "Q1") (pin "B") (pinfunction "B_B") (pintype "bidirectional"))
      (node (ref "R1") (pin "P$2") (pinfunction "P$2_P$2") (pintype "bidirectional"))
    )
    (net (code "42") (name "Net-(Q2-PadC)") (class "Default")
      (node (ref "Q2") (pin "C") (pinfunction "C_C") (pintype "bidirectional"))
      (node (ref "Q3") (pin "B") (pinfunction "B_B") (pintype "bidirectional"))
    )
    (net (code "43") (name "Net-(Q2-PadE)") (class "Default")
      (node (ref "Q2") (pin "E") (pinfunction "E_E") (pintype "bidirectional"))
      (node (ref "R10") (pin "P$1") (pinfunction "P$1_P$1") (pintype "bidirectional"))
    )
    (net (code "44") (name "Net-(Q4-PadB)") (class "Default")
      (node (ref "Q4") (pin "B") (pinfunction "B_B") (pintype "bidirectional"))
      (node (ref "R14") (pin "P$2") (pinfunction "P$2_P$2") (pintype "bidirectional"))
    )
    (net (code "45") (name "Net-(Q4-PadC)") (class "Default")
      (node (ref "Q4") (pin "C") (pinfunction "C_C") (pintype "bidirectional"))
      (node (ref "R15") (pin "P$1") (pinfunction "P$1_P$1") (pintype "bidirectional"))
    )
    (net (code "46") (name "Net-(R4-PadP$1)") (class "Default")
      (node (ref "R4") (pin "P$1") (pinfunction "P$1_P$1") (pintype "bidirectional"))
      (node (ref "U1") (pin "IO16") (pinfunction "IO16_IO16") (pintype "bidirectional"))
    )
    (net (code "47") (name "Net-(R5-PadP$1)") (class "Default")
      (node (ref "R5") (pin "P$1") (pinfunction "P$1_P$1") (pintype "bidirectional"))
      (node (ref "U1") (pin "IO19") (pinfunction "IO19_IO19") (pintype "bidirectional"))
    )
    (net (code "48") (name "Net-(R6-PadP3)") (class "Default")
      (node (ref "R6") (pin "P3") (pinfunction "P3_P3") (pintype "bidirectional"))
      (node (ref "U1") (pin "IO2") (pinfunction "IO2_IO2") (pintype "bidirectional"))
    )
    (net (code "49") (name "Net-(R7-PadP$1)") (class "Default")
      (node (ref "R7") (pin "P$1") (pinfunction "P$1_P$1") (pintype "bidirectional"))
      (node (ref "U1") (pin "IO21") (pinfunction "IO21_IO21") (pintype "bidirectional"))
    )
    (net (code "50") (name "Net-(R8-PadP$1)") (class "Default")
      (node (ref "R8") (pin "P$1") (pinfunction "P$1_P$1") (pintype "bidirectional"))
      (node (ref "U1") (pin "IO18") (pinfunction "IO18_IO18") (pintype "bidirectional"))
    )
    (net (code "51") (name "Net-(R11-PadP$1)") (class "Default")
      (node (ref "R11") (pin "P$1") (pinfunction "P$1_P$1") (pintype "bidirectional"))
      (node (ref "R9") (pin "P1") (pinfunction "P1_P1") (pintype "bidirectional"))
    )
    (net (code "52") (name "Net-(R17-PadP3)") (class "Default")
      (node (ref "R17") (pin "P3") (pinfunction "P3_P3") (pintype "bidirectional"))
      (node (ref "U6") (pin "GND") (pinfunction "GND_GND") (pintype "power_in"))
    )
    (net (code "53") (name "Net-(U2-EMI_OUT)") (class "Default")
      (node (ref "Q2") (pin "B") (pinfunction "B_B") (pintype "bidirectional"))
      (node (ref "U2") (pin "PIN_1") (pinfunction "EMI_OUT_PIN_1") (pintype "output"))
    )
    (net (code "54") (name "Net-(U2-IN+)") (class "Default")
      (node (ref "C1") (pin "P$2") (pinfunction "P$2_P$2") (pintype "bidirectional"))
      (node (ref "R3") (pin "P$1") (pinfunction "P$1_P$1") (pintype "bidirectional"))
      (node (ref "U2") (pin "PIN_2") (pinfunction "IN+_PIN_2") (pintype "input"))
    )
    (net (code "55") (name "Net-(U3-CONT)") (class "Default")
      (node (ref "C3") (pin "P$1") (pinfunction "P$1_P$1") (pintype "bidirectional"))
      (node (ref "U3") (pin "PIN_5") (pinfunction "CONT_PIN_5") (pintype "bidirectional"))
    )
    (net (code "56") (name "Net-(U3-DISCH)") (class "Default")
      (node (ref "D3") (pin "P$1") (pinfunction "P$1_P$1") (pintype "bidirectional"))
      (node (ref "R9") (pin "P3") (pinfunction "P3_P3") (pintype "bidirectional"))
      (node (ref "U3") (pin "PIN_7") (pinfunction "DISCH_PIN_7") (pintype "bidirectional"))
    )
    (net (code "57") (name "Net-(U3-OUT)") (class "Default")
      (node (ref "R14") (pin "P$1") (pinfunction "P$1_P$1") (pintype "bidirectional"))
      (node (ref "U3") (pin "PIN_3") (pinfunction "OUT_PIN_3") (pintype "output"))
    )
    (net (code "58") (name "Net-(U3-THRES)") (class "Default")
      (node (ref "C4") (pin "P$2") (pinfunction "P$2_P$2") (pintype "bidirectional"))
      (node (ref "D2") (pin "P$1") (pinfunction "P$1_P$1") (pintype "bidirectional"))
      (node (ref "D3") (pin "P$2") (pinfunction "P$2_P$2") (pintype "bidirectional"))
      (node (ref "U3") (pin "PIN_2") (pinfunction "TRIG_PIN_2") (pintype "bidirectional"))
      (node (ref "U3") (pin "PIN_6") (pinfunction "THRES_PIN_6") (pintype "bidirectional"))
    )
    (net (code "59") (name "Net-(U4-1Y)") (class "Default")
      (node (ref "U4") (pin "PIN_3") (pinfunction "1Y_PIN_3") (pintype "output"))
      (node (ref "U4") (pin "PIN_4") (pinfunction "2A_PIN_4") (pintype "input"))
    )
    (net (code "60") (name "Net-(U4-2Y)") (class "Default")
      (node (ref "U4") (pin "PIN_12") (pinfunction "4B_PIN_12") (pintype "input"))
      (node (ref "U4") (pin "PIN_6") (pinfunction "2Y_PIN_6") (pintype "output"))
    )
    (net (code "61") (name "Net-(U4-3A)") (class "Default")
      (node (ref "U4") (pin "PIN_10") (pinfunction "3A_PIN_10") (pintype "input"))
      (node (ref "U4") (pin "PIN_11") (pinfunction "4Y_PIN_11") (pintype "output"))
    )
    (net (code "62") (name "Net-(U7-A+)") (class "Default")
      (node (ref "C8") (pin "P$2") (pinfunction "P$2_P$2") (pintype "bidirectional"))
      (node (ref "R19") (pin "P$2") (pinfunction "P$2_P$2") (pintype "bidirectional"))
      (node (ref "U7") (pin "PIN_3") (pinfunction "A+_PIN_3") (pintype "input"))
    )
    (net (code "63") (name "Net-(U7-A-)") (class "Default")
      (node (ref "R20") (pin "P3") (pinfunction "P3_P3") (pintype "bidirectional"))
      (node (ref "U7") (pin "PIN_2") (pinfunction "A-_PIN_2") (pintype "input"))
    )
    (net (code "64") (name "Net-(U7-A_OUT)") (class "Default")
      (node (ref "C11") (pin "P$1") (pinfunction "P$1_P$1") (pintype "bidirectional"))
      (node (ref "R20") (pin "P1") (pinfunction "P1_P1") (pintype "bidirectional"))
      (node (ref "U7") (pin "PIN_1") (pinfunction "A_OUT_PIN_1") (pintype "output"))
    )
    (net (code "65") (name "Net-(U7-B+)") (class "Default")
      (node (ref "C11") (pin "P$2") (pinfunction "P$2_P$2") (pintype "bidirectional"))
      (node (ref "R22") (pin "P$1") (pinfunction "P$1_P$1") (pintype "bidirectional"))
      (node (ref "U7") (pin "PIN_5") (pinfunction "B+_PIN_5") (pintype "input"))
    )
    (net (code "66") (name "Net-(U7-B-)") (class "Default")
      (node (ref "R23") (pin "P3") (pinfunction "P3_P3") (pintype "bidirectional"))
      (node (ref "U7") (pin "PIN_6") (pinfunction "B-_PIN_6") (pintype "input"))
    )
    (net (code "67") (name "VCC") (class "Default")
      (node (ref "ACDC1") (pin "220V_L") (pinfunction "220V_L_220V_L") (pintype "power_in"))
      (node (ref "ACDC1") (pin "220V_N") (pinfunction "220V_N_220V_N") (pintype "power_in"))
    )
    (net (code "68") (name "unconnected-(J10-PadNC1)") (class "Default")
      (node (ref "J10") (pin "NC1") (pinfunction "NC1_NC1") (pintype "no_connect"))
    )
    (net (code "69") (name "unconnected-(U1-PadCLK)") (class "Default")
      (node (ref "U1") (pin "CLK") (pinfunction "CLK_CLK") (pintype "bidirectional"))
    )
    (net (code "70") (name "unconnected-(U1-PadCMD)") (class "Default")
      (node (ref "U1") (pin "CMD") (pinfunction "CMD_CMD") (pintype "bidirectional"))
    )
    (net (code "71") (name "unconnected-(U1-PadEN)") (class "Default")
      (node (ref "U1") (pin "EN") (pinfunction "EN_EN") (pintype "bidirectional"))
    )
    (net (code "72") (name "unconnected-(U1-PadGND_1)") (class "Default")
      (node (ref "U1") (pin "GND_1") (pinfunction "GND_1_GND_1") (pintype "bidirectional"))
    )
    (net (code "73") (name "unconnected-(U1-PadGND_2)") (class "Default")
      (node (ref "U1") (pin "GND_2") (pinfunction "GND_2_GND_2") (pintype "bidirectional"))
    )
    (net (code "74") (name "unconnected-(U1-PadIO0)") (class "Default")
      (node (ref "U1") (pin "IO0") (pinfunction "IO0_IO0") (pintype "bidirectional"))
    )
    (net (code "75") (name "unconnected-(U1-PadIO5)") (class "Default")
      (node (ref "U1") (pin "IO5") (pinfunction "IO5_IO5") (pintype "bidirectional"))
    )
    (net (code "76") (name "unconnected-(U1-PadIO12)") (class "Default")
      (node (ref "U1") (pin "IO12") (pinfunction "IO12_IO12") (pintype "bidirectional"))
    )
    (net (code "77") (name "unconnected-(U1-PadIO13)") (class "Default")
      (node (ref "U1") (pin "IO13") (pinfunction "IO13_IO13") (pintype "bidirectional"))
    )
    (net (code "78") (name "unconnected-(U1-PadIO14)") (class "Default")
      (node (ref "U1") (pin "IO14") (pinfunction "IO14_IO14") (pintype "bidirectional"))
    )
    (net (code "79") (name "unconnected-(U1-PadIO17)") (class "Default")
      (node (ref "U1") (pin "IO17") (pinfunction "IO17_IO17") (pintype "bidirectional"))
    )
    (net (code "80") (name "unconnected-(U1-PadIO22)") (class "Default")
      (node (ref "U1") (pin "IO22") (pinfunction "IO22_IO22") (pintype "bidirectional"))
    )
    (net (code "81") (name "unconnected-(U1-PadIO23)") (class "Default")
      (node (ref "U1") (pin "IO23") (pinfunction "IO23_IO23") (pintype "bidirectional"))
    )
    (net (code "82") (name "unconnected-(U1-PadIO25)") (class "Default")
      (node (ref "U1") (pin "IO25") (pinfunction "IO25_IO25") (pintype "bidirectional"))
    )
    (net (code "83") (name "unconnected-(U1-PadIO26)") (class "Default")
      (node (ref "U1") (pin "IO26") (pinfunction "IO26_IO26") (pintype "bidirectional"))
    )
    (net (code "84") (name "unconnected-(U1-PadIO27)") (class "Default")
      (node (ref "U1") (pin "IO27") (pinfunction "IO27_IO27") (pintype "bidirectional"))
    )
    (net (code "85") (name "unconnected-(U1-PadIO32)") (class "Default")
      (node (ref "U1") (pin "IO32") (pinfunction "IO32_IO32") (pintype "bidirectional"))
    )
    (net (code "86") (name "unconnected-(U1-PadIO34)") (class "Default")
      (node (ref "U1") (pin "IO34") (pinfunction "IO34_IO34") (pintype "bidirectional"))
    )
    (net (code "87") (name "unconnected-(U1-PadIO35)") (class "Default")
      (node (ref "U1") (pin "IO35") (pinfunction "IO35_IO35") (pintype "bidirectional"))
    )
    (net (code "88") (name "unconnected-(U1-PadSD0)") (class "Default")
      (node (ref "U1") (pin "SD0") (pinfunction "SD0_SD0") (pintype "bidirectional"))
    )
    (net (code "89") (name "unconnected-(U1-PadSD1)") (class "Default")
      (node (ref "U1") (pin "SD1") (pinfunction "SD1_SD1") (pintype "bidirectional"))
    )
    (net (code "90") (name "unconnected-(U1-PadSD2)") (class "Default")
      (node (ref "U1") (pin "SD2") (pinfunction "SD2_SD2") (pintype "bidirectional"))
    )
    (net (code "91") (name "unconnected-(U1-PadSD3)") (class "Default")
      (node (ref "U1") (pin "SD3") (pinfunction "SD3_SD3") (pintype "bidirectional"))
    )
    (net (code "92") (name "unconnected-(U1-PadSVN)") (class "Default")
      (node (ref "U1") (pin "SVN") (pinfunction "SVN_SVN") (pintype "bidirectional"))
    )
    (net (code "93") (name "unconnected-(U1-PadSVP)") (class "Default")
      (node (ref "U1") (pin "SVP") (pinfunction "SVP_SVP") (pintype "bidirectional"))
    )
    (net (code "94") (name "unconnected-(U1-PadTXD0)") (class "Default")
      (node (ref "U1") (pin "TXD0") (pinfunction "TXD0_TXD0") (pintype "bidirectional"))
    )
    (net (code "95") (name "unconnected-(U1-RXD0-PadRXD)") (class "Default")
      (node (ref "U1") (pin "RXD") (pinfunction "RXD0_RXD") (pintype "bidirectional"))
    )
    (net (code "96") (name "unconnected-(U2-BALANCE-PadPIN_5)") (class "Default")
      (node (ref "U2") (pin "PIN_5") (pinfunction "BALANCE_PIN_5") (pintype "input"))
    )
    (net (code "97") (name "unconnected-(U2-BAL_STROBE-PadPIN_6)") (class "Default")
      (node (ref "U2") (pin "PIN_6") (pinfunction "BAL_STROBE_PIN_6") (pintype "input"))
    )
    (net (code "98") (name "unconnected-(U2-COL_OUT-PadPIN_7)") (class "Default")
      (node (ref "U2") (pin "PIN_7") (pinfunction "COL_OUT_PIN_7") (pintype "output"))
    )
    (net (code "99") (name "unconnected-(U8-PadPB0)") (class "Default")
      (node (ref "U8") (pin "PB0") (pinfunction "PB0_PB0") (pintype "bidirectional"))
    )
    (net (code "100") (name "unconnected-(U8-PadPB1)") (class "Default")
      (node (ref "U8") (pin "PB1") (pinfunction "PB1_PB1") (pintype "bidirectional"))
    )
    (net (code "101") (name "unconnected-(U8-PadPB2)") (class "Default")
      (node (ref "U8") (pin "PB2") (pinfunction "PB2_PB2") (pintype "bidirectional"))
    )
    (net (code "102") (name "unconnected-(U8-PadPB6)") (class "Default")
      (node (ref "U8") (pin "PB6") (pinfunction "PB6_PB6") (pintype "bidirectional"))
    )
    (net (code "103") (name "unconnected-(U8-PadPB7)") (class "Default")
      (node (ref "U8") (pin "PB7") (pinfunction "PB7_PB7") (pintype "bidirectional"))
    )
    (net (code "104") (name "unconnected-(U8-PadPC0)") (class "Default")
      (node (ref "U8") (pin "PC0") (pinfunction "PC0_PC0") (pintype "bidirectional"))
    )
    (net (code "105") (name "unconnected-(U8-PadPC2)") (class "Default")
      (node (ref "U8") (pin "PC2") (pinfunction "PC2_PC2") (pintype "bidirectional"))
    )
    (net (code "106") (name "unconnected-(U8-PadPD2)") (class "Default")
      (node (ref "U8") (pin "PD2") (pinfunction "PD2_PD2") (pintype "bidirectional"))
    )
    (net (code "107") (name "unconnected-(U8-PadPD3)") (class "Default")
      (node (ref "U8") (pin "PD3") (pinfunction "PD3_PD3") (pintype "bidirectional"))
    )
    (net (code "108") (name "unconnected-(U8-PadPD4)") (class "Default")
      (node (ref "U8") (pin "PD4") (pinfunction "PD4_PD4") (pintype "bidirectional"))
    )
    (net (code "109") (name "unconnected-(U8-PadPD5)") (class "Default")
      (node (ref "U8") (pin "PD5") (pinfunction "PD5_PD5") (pintype "bidirectional"))
    )
    (net (code "110") (name "unconnected-(U8-PadPD6)") (class "Default")
      (node (ref "U8") (pin "PD6") (pinfunction "PD6_PD6") (pintype "bidirectional"))
    )
    (net (code "111") (name "unconnected-(U8-PadPD7)") (class "Default")
      (node (ref "U8") (pin "PD7") (pinfunction "PD7_PD7") (pintype "bidirectional"))
    )
  )
)
